# Sch_BuckXL6009.net
KiCad netlist of a schematic drawn in Altium Designer
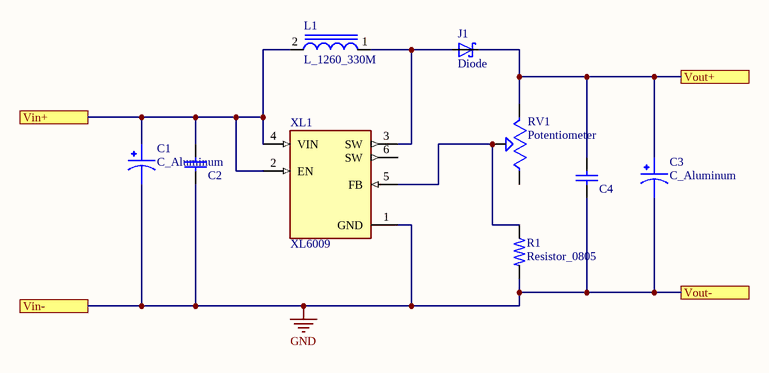
[diagram p0: Sch_BuckXL6009.SchDoc]

(export (version "E")
  (design (tool "Eeschema 10.0.6"))
  (components
    (comp (ref "C1")
      (value "C_Aluminum")
      (footprint "C_Aluminum")
      (description "220ÂµF 50V Aluminum Electrolytic Capacitors Radial, Can - SMD 1000 Hrs @ 105Â°C")
      (fields (field (name "MF") "Nichicon") (field (name "MP") "UWT1H221MNL1GS"))
      (libsource (lib "Lib_RLC") (part "C_Aluminum"))
    )
    (comp (ref "C2")
      (value "Capacitor Ceramic")
      (footprint "CAP_0805")
      (description "Capacitor")
      (fields (field (name "PUBLISHER") "Altium Limited"))
      (libsource (lib "Lib_RLC") (part "Capacitor SMD"))
    )
    (comp (ref "C3")
      (value "C_Aluminum")
      (footprint "C_Aluminum")
      (description "220ÂµF 50V Aluminum Electrolytic Capacitors Radial, Can - SMD 1000 Hrs @ 105Â°C")
      (fields (field (name "MF") "Nichicon") (field (name "MP") "UWT1H221MNL1GS"))
      (libsource (lib "Lib_RLC") (part "C_Aluminum"))
    )
    (comp (ref "C4")
      (value "Capacitor Ceramic")
      (footprint "CAP_0805")
      (description "Capacitor")
      (fields (field (name "PUBLISHER") "Altium Limited"))
      (libsource (lib "Lib_RLC") (part "Capacitor SMD"))
    )
    (comp (ref "J1")
      (value "Diode")
      (footprint "Diode(Wr)")
      (fields (field (name "MP") "SS34") (field (name "MF") "ON Semiconductor"))
      (libsource (lib "Lib_RLC") (part "Diode"))
    )
    (comp (ref "L1")
      (value "L_1260_330M")
      (footprint "L_1260_330M")
      (description "33ÂµH Shielded Wirewound Inductor 3A 60mOhm Max Nonstandard")
      (fields (field (name "MF") "Bourns") (field (name "MP") "SRR1260-330M"))
      (libsource (lib "Lib_RLC") (part "L_1260_330M"))
    )
    (comp (ref "R1")
      (value "Resistor_0805")
      (footprint "Resistor_0805")
      (description "CRG0805 1% 24K")
      (fields (field (name "MP") "1623163-1"))
      (libsource (lib "Lib_RLC") (part "Resistor_0805"))
    )
    (comp (ref "RV1")
      (value "Potentiometer")
      (footprint "Potentiometer_ThroughHole")
      (description "25 kOhms 0.5W, 1/2W PC Pins Through Hole Trimmer Potentiometer Cermet 25 Turn Top Adjustment")
      (fields (field (name "MF") "Bourns") (field (name "MP") "PV36W253C01B00"))
      (libsource (lib "Lib_RLC") (part "Potentiometer_ThroughHole"))
    )
    (comp (ref "XL1")
      (value "XL6009")
      (footprint "XL6009")
      (fields (field (name "MF") "XLSEMI"))
      (libsource (lib "Lib_RLC") (part "XL6009"))
    )
  )
  (nets
    (net (code "1") (name "/Vin+") (class "Default")
      (node (ref "C1") (pin "1") (pinfunction "1_1") (pintype "passive"))
      (node (ref "C2") (pin "2") (pinfunction "2_2") (pintype "passive"))
      (node (ref "L1") (pin "2") (pinfunction "2_2") (pintype "passive"))
      (node (ref "XL1") (pin "2") (pinfunction "EN_2") (pintype "input"))
      (node (ref "XL1") (pin "4") (pinfunction "VIN_4") (pintype "input"))
    )
    (net (code "2") (name "/Vout+") (class "Default")
      (node (ref "C3") (pin "1") (pinfunction "1_1") (pintype "passive"))
      (node (ref "C4") (pin "2") (pinfunction "2_2") (pintype "passive"))
      (node (ref "J1") (pin "C") (pinfunction "C_C") (pintype "passive"))
      (node (ref "RV1") (pin "3") (pinfunction "3_3") (pintype "passive"))
    )
    (net (code "3") (name "GND") (class "Default")
      (node (ref "C1") (pin "2") (pinfunction "2_2") (pintype "passive"))
      (node (ref "C2") (pin "1") (pinfunction "1_1") (pintype "passive"))
      (node (ref "C3") (pin "2") (pinfunction "2_2") (pintype "passive"))
      (node (ref "C4") (pin "1") (pinfunction "1_1") (pintype "passive"))
      (node (ref "R1") (pin "2") (pinfunction "2_2") (pintype "passive"))
      (node (ref "XL1") (pin "1") (pinfunction "GND_1") (pintype "power_in"))
    )
    (net (code "4") (name "Net-(J1-PadA)") (class "Default")
      (node (ref "J1") (pin "A") (pinfunction "A_A") (pintype "passive"))
      (node (ref "L1") (pin "1") (pinfunction "1_1") (pintype "passive"))
      (node (ref "XL1") (pin "3") (pinfunction "SW_3") (pintype "output"))
    )
    (net (code "5") (name "Net-(XL1-FB)") (class "Default")
      (node (ref "R1") (pin "1") (pinfunction "1_1") (pintype "passive"))
      (node (ref "RV1") (pin "2") (pinfunction "2_2") (pintype "passive"))
      (node (ref "XL1") (pin "5") (pinfunction "FB_5") (pintype "input"))
    )
    (net (code "6") (name "unconnected-(RV1-Pad1)") (class "Default")
      (node (ref "RV1") (pin "1") (pinfunction "1_1") (pintype "passive"))
    )
    (net (code "7") (name "unconnected-(XL1-SW-Pad6)") (class "Default")
      (node (ref "XL1") (pin "6") (pinfunction "SW_6") (pintype "output"))
    )
  )
)
